# basic.net
KiCad netlist of a schematic drawn in EAGLE
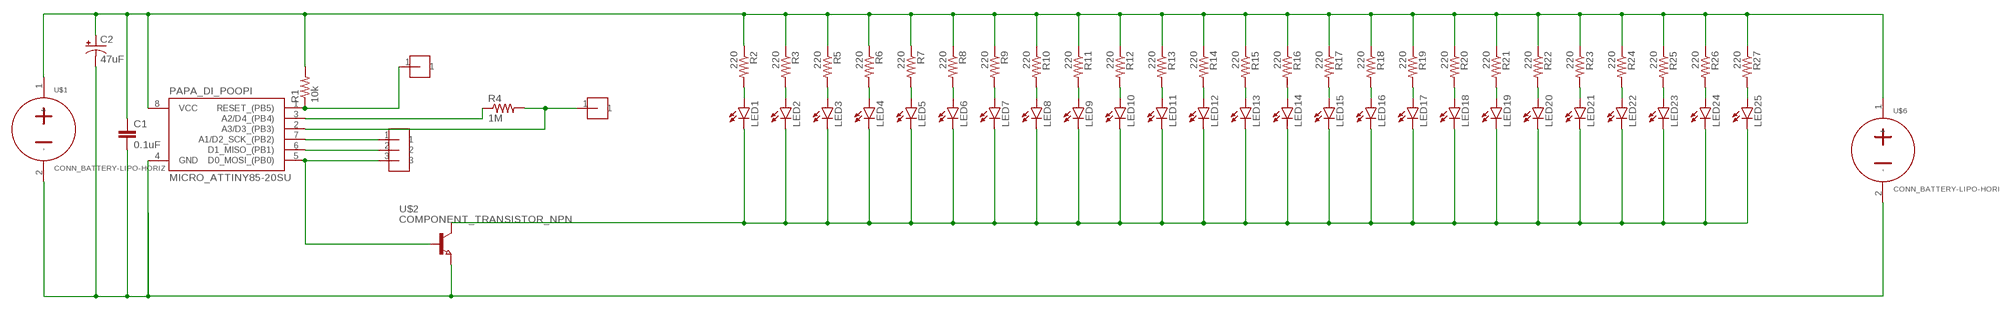
[diagram p0: schematic, sheet 1]

(export (version "E")
  (design (tool "Eeschema 10.0.6"))
  (components
    (comp (ref "C1")
      (value "0.1uF")
      (footprint "eagle-import:0805")
      (libsource (lib "eagle-import") (part "COMPONENT_CAP-0805"))
    )
    (comp (ref "C2")
      (value "47uF")
      (footprint "eagle-import:CAP_RADIAL_CAN_10MM")
      (libsource (lib "eagle-import") (part "COMPONENT_CAP_POL-6.3MM"))
    )
    (comp (ref "CAP_SENSOR_1")
      (value "HEADER-1-TESTPOINT")
      (footprint "eagle-import:TESTPOINT-1")
      (libsource (lib "eagle-import") (part "HEADER-1-TESTPOINT"))
    )
    (comp (ref "CAP_SENSOR_2")
      (value "HEADER-1-TESTPOINT")
      (footprint "eagle-import:TESTPOINT-1")
      (libsource (lib "eagle-import") (part "HEADER-1-TESTPOINT"))
    )
    (comp (ref "LED1")
      (value "LED-0805")
      (footprint "eagle-import:CHIP-LED0805")
      (libsource (lib "eagle-import") (part "LED-0805"))
    )
    (comp (ref "LED2")
      (value "LED-0805")
      (footprint "eagle-import:CHIP-LED0805")
      (libsource (lib "eagle-import") (part "LED-0805"))
    )
    (comp (ref "LED3")
      (value "LED-0805")
      (footprint "eagle-import:CHIP-LED0805")
      (libsource (lib "eagle-import") (part "LED-0805"))
    )
    (comp (ref "LED4")
      (value "LED-0805")
      (footprint "eagle-import:CHIP-LED0805")
      (libsource (lib "eagle-import") (part "LED-0805"))
    )
    (comp (ref "LED5")
      (value "LED-0805")
      (footprint "eagle-import:CHIP-LED0805")
      (libsource (lib "eagle-import") (part "LED-0805"))
    )
    (comp (ref "LED6")
      (value "LED-0805")
      (footprint "eagle-import:CHIP-LED0805")
      (libsource (lib "eagle-import") (part "LED-0805"))
    )
    (comp (ref "LED7")
      (value "LED-0805")
      (footprint "eagle-import:CHIP-LED0805")
      (libsource (lib "eagle-import") (part "LED-0805"))
    )
    (comp (ref "LED8")
      (value "LED-0805")
      (footprint "eagle-import:CHIP-LED0805")
      (libsource (lib "eagle-import") (part "LED-0805"))
    )
    (comp (ref "LED9")
      (value "LED-0805")
      (footprint "eagle-import:CHIP-LED0805")
      (libsource (lib "eagle-import") (part "LED-0805"))
    )
    (comp (ref "LED10")
      (value "LED-0805")
      (footprint "eagle-import:CHIP-LED0805")
      (libsource (lib "eagle-import") (part "LED-0805"))
    )
    (comp (ref "LED11")
      (value "LED-0805")
      (footprint "eagle-import:CHIP-LED0805")
      (libsource (lib "eagle-import") (part "LED-0805"))
    )
    (comp (ref "LED12")
      (value "LED-0805")
      (footprint "eagle-import:CHIP-LED0805")
      (libsource (lib "eagle-import") (part "LED-0805"))
    )
    (comp (ref "LED13")
      (value "LED-0805")
      (footprint "eagle-import:CHIP-LED0805")
      (libsource (lib "eagle-import") (part "LED-0805"))
    )
    (comp (ref "LED14")
      (value "LED-0805")
      (footprint "eagle-import:CHIP-LED0805")
      (libsource (lib "eagle-import") (part "LED-0805"))
    )
    (comp (ref "LED15")
      (value "LED-0805")
      (footprint "eagle-import:CHIP-LED0805")
      (libsource (lib "eagle-import") (part "LED-0805"))
    )
    (comp (ref "LED16")
      (value "LED-0805")
      (footprint "eagle-import:CHIP-LED0805")
      (libsource (lib "eagle-import") (part "LED-0805"))
    )
    (comp (ref "LED17")
      (value "LED-0805")
      (footprint "eagle-import:CHIP-LED0805")
      (libsource (lib "eagle-import") (part "LED-0805"))
    )
    (comp (ref "LED18")
      (value "LED-0805")
      (footprint "eagle-import:CHIP-LED0805")
      (libsource (lib "eagle-import") (part "LED-0805"))
    )
    (comp (ref "LED19")
      (value "LED-0805")
      (footprint "eagle-import:CHIP-LED0805")
      (libsource (lib "eagle-import") (part "LED-0805"))
    )
    (comp (ref "LED20")
      (value "LED-0805")
      (footprint "eagle-import:CHIP-LED0805")
      (libsource (lib "eagle-import") (part "LED-0805"))
    )
    (comp (ref "LED21")
      (value "LED-0805")
      (footprint "eagle-import:CHIP-LED0805")
      (libsource (lib "eagle-import") (part "LED-0805"))
    )
    (comp (ref "LED22")
      (value "LED-0805")
      (footprint "eagle-import:CHIP-LED0805")
      (libsource (lib "eagle-import") (part "LED-0805"))
    )
    (comp (ref "LED23")
      (value "LED-0805")
      (footprint "eagle-import:CHIP-LED0805")
      (libsource (lib "eagle-import") (part "LED-0805"))
    )
    (comp (ref "LED24")
      (value "LED-0805")
      (footprint "eagle-import:CHIP-LED0805")
      (libsource (lib "eagle-import") (part "LED-0805"))
    )
    (comp (ref "LED25")
      (value "LED-0805")
      (footprint "eagle-import:CHIP-LED0805")
      (libsource (lib "eagle-import") (part "LED-0805"))
    )
    (comp (ref "PAPA_DI_POOPI")
      (value "MICRO_ATTINY85-20SU")
      (footprint "eagle-import:SOIC8")
      (libsource (lib "eagle-import") (part "MICRO_ATTINY85-20SU"))
    )
    (comp (ref "R1")
      (value "10k")
      (footprint "eagle-import:0805")
      (libsource (lib "eagle-import") (part "COMPONENT_RESISTOR-0805"))
    )
    (comp (ref "R2")
      (value "220")
      (footprint "eagle-import:0805")
      (libsource (lib "eagle-import") (part "COMPONENT_RESISTOR-0805"))
    )
    (comp (ref "R3")
      (value "220")
      (footprint "eagle-import:0805")
      (libsource (lib "eagle-import") (part "COMPONENT_RESISTOR-0805"))
    )
    (comp (ref "R4")
      (value "1M")
      (footprint "eagle-import:0805")
      (libsource (lib "eagle-import") (part "COMPONENT_RESISTOR-0805"))
    )
    (comp (ref "R5")
      (value "220")
      (footprint "eagle-import:0805")
      (libsource (lib "eagle-import") (part "COMPONENT_RESISTOR-0805"))
    )
    (comp (ref "R6")
      (value "220")
      (footprint "eagle-import:0805")
      (libsource (lib "eagle-import") (part "COMPONENT_RESISTOR-0805"))
    )
    (comp (ref "R7")
      (value "220")
      (footprint "eagle-import:0805")
      (libsource (lib "eagle-import") (part "COMPONENT_RESISTOR-0805"))
    )
    (comp (ref "R8")
      (value "220")
      (footprint "eagle-import:0805")
      (libsource (lib "eagle-import") (part "COMPONENT_RESISTOR-0805"))
    )
    (comp (ref "R9")
      (value "220")
      (footprint "eagle-import:0805")
      (libsource (lib "eagle-import") (part "COMPONENT_RESISTOR-0805"))
    )
    (comp (ref "R10")
      (value "220")
      (footprint "eagle-import:0805")
      (libsource (lib "eagle-import") (part "COMPONENT_RESISTOR-0805"))
    )
    (comp (ref "R11")
      (value "220")
      (footprint "eagle-import:0805")
      (libsource (lib "eagle-import") (part "COMPONENT_RESISTOR-0805"))
    )
    (comp (ref "R12")
      (value "220")
      (footprint "eagle-import:0805")
      (libsource (lib "eagle-import") (part "COMPONENT_RESISTOR-0805"))
    )
    (comp (ref "R13")
      (value "220")
      (footprint "eagle-import:0805")
      (libsource (lib "eagle-import") (part "COMPONENT_RESISTOR-0805"))
    )
    (comp (ref "R14")
      (value "220")
      (footprint "eagle-import:0805")
      (libsource (lib "eagle-import") (part "COMPONENT_RESISTOR-0805"))
    )
    (comp (ref "R15")
      (value "220")
      (footprint "eagle-import:0805")
      (libsource (lib "eagle-import") (part "COMPONENT_RESISTOR-0805"))
    )
    (comp (ref "R16")
      (value "220")
      (footprint "eagle-import:0805")
      (libsource (lib "eagle-import") (part "COMPONENT_RESISTOR-0805"))
    )
    (comp (ref "R17")
      (value "220")
      (footprint "eagle-import:0805")
      (libsource (lib "eagle-import") (part "COMPONENT_RESISTOR-0805"))
    )
    (comp (ref "R18")
      (value "220")
      (footprint "eagle-import:0805")
      (libsource (lib "eagle-import") (part "COMPONENT_RESISTOR-0805"))
    )
    (comp (ref "R19")
      (value "220")
      (footprint "eagle-import:0805")
      (libsource (lib "eagle-import") (part "COMPONENT_RESISTOR-0805"))
    )
    (comp (ref "R20")
      (value "220")
      (footprint "eagle-import:0805")
      (libsource (lib "eagle-import") (part "COMPONENT_RESISTOR-0805"))
    )
    (comp (ref "R21")
      (value "220")
      (footprint "eagle-import:0805")
      (libsource (lib "eagle-import") (part "COMPONENT_RESISTOR-0805"))
    )
    (comp (ref "R22")
      (value "220")
      (footprint "eagle-import:0805")
      (libsource (lib "eagle-import") (part "COMPONENT_RESISTOR-0805"))
    )
    (comp (ref "R23")
      (value "220")
      (footprint "eagle-import:0805")
      (libsource (lib "eagle-import") (part "COMPONENT_RESISTOR-0805"))
    )
    (comp (ref "R24")
      (value "220")
      (footprint "eagle-import:0805")
      (libsource (lib "eagle-import") (part "COMPONENT_RESISTOR-0805"))
    )
    (comp (ref "R25")
      (value "220")
      (footprint "eagle-import:0805")
      (libsource (lib "eagle-import") (part "COMPONENT_RESISTOR-0805"))
    )
    (comp (ref "R26")
      (value "220")
      (footprint "eagle-import:0805")
      (libsource (lib "eagle-import") (part "COMPONENT_RESISTOR-0805"))
    )
    (comp (ref "R27")
      (value "220")
      (footprint "eagle-import:0805")
      (libsource (lib "eagle-import") (part "COMPONENT_RESISTOR-0805"))
    )
    (comp (ref "U$1")
      (value "CONN_BATTERY-LIPO-HORIZ")
      (footprint "eagle-import:JST-PH-2-SMT-RA")
      (libsource (lib "eagle-import") (part "CONN_BATTERY-LIPO-HORIZ"))
    )
    (comp (ref "U$2")
      (value "COMPONENT_TRANSISTOR_NPN")
      (footprint "eagle-import:SOT23")
      (libsource (lib "eagle-import") (part "COMPONENT_TRANSISTOR_NPN"))
    )
    (comp (ref "U$5")
      (value "HEADER-3-TESTPOINT")
      (footprint "eagle-import:TESTPOINT-3")
      (libsource (lib "eagle-import") (part "HEADER-3-TESTPOINT"))
    )
    (comp (ref "U$6")
      (value "CONN_BATTERY-LIPO-HORIZ")
      (footprint "eagle-import:JST-PH-2-SMT-RA")
      (libsource (lib "eagle-import") (part "CONN_BATTERY-LIPO-HORIZ"))
    )
  )
  (nets
    (net (code "1") (name "Net-(LED1-PadA)") (class "Default")
      (node (ref "LED1") (pin "A") (pinfunction "A_A") (pintype "passive"))
      (node (ref "R2") (pin "2") (pinfunction "2_2") (pintype "passive"))
    )
    (net (code "2") (name "Net-(LED2-PadA)") (class "Default")
      (node (ref "LED2") (pin "A") (pinfunction "A_A") (pintype "passive"))
      (node (ref "R3") (pin "2") (pinfunction "2_2") (pintype "passive"))
    )
    (net (code "3") (name "Net-(LED3-PadA)") (class "Default")
      (node (ref "LED3") (pin "A") (pinfunction "A_A") (pintype "passive"))
      (node (ref "R5") (pin "2") (pinfunction "2_2") (pintype "passive"))
    )
    (net (code "4") (name "Net-(LED4-PadA)") (class "Default")
      (node (ref "LED4") (pin "A") (pinfunction "A_A") (pintype "passive"))
      (node (ref "R6") (pin "2") (pinfunction "2_2") (pintype "passive"))
    )
    (net (code "5") (name "Net-(LED5-PadA)") (class "Default")
      (node (ref "LED5") (pin "A") (pinfunction "A_A") (pintype "passive"))
      (node (ref "R7") (pin "2") (pinfunction "2_2") (pintype "passive"))
    )
    (net (code "6") (name "Net-(LED6-PadA)") (class "Default")
      (node (ref "LED6") (pin "A") (pinfunction "A_A") (pintype "passive"))
      (node (ref "R8") (pin "2") (pinfunction "2_2") (pintype "passive"))
    )
    (net (code "7") (name "Net-(LED7-PadA)") (class "Default")
      (node (ref "LED7") (pin "A") (pinfunction "A_A") (pintype "passive"))
      (node (ref "R9") (pin "2") (pinfunction "2_2") (pintype "passive"))
    )
    (net (code "8") (name "Net-(LED8-PadA)") (class "Default")
      (node (ref "LED8") (pin "A") (pinfunction "A_A") (pintype "passive"))
      (node (ref "R10") (pin "2") (pinfunction "2_2") (pintype "passive"))
    )
    (net (code "9") (name "Net-(LED9-PadA)") (class "Default")
      (node (ref "LED9") (pin "A") (pinfunction "A_A") (pintype "passive"))
      (node (ref "R11") (pin "2") (pinfunction "2_2") (pintype "passive"))
    )
    (net (code "10") (name "Net-(LED10-PadA)") (class "Default")
      (node (ref "LED10") (pin "A") (pinfunction "A_A") (pintype "passive"))
      (node (ref "R12") (pin "2") (pinfunction "2_2") (pintype "passive"))
    )
    (net (code "11") (name "Net-(LED11-PadA)") (class "Default")
      (node (ref "LED11") (pin "A") (pinfunction "A_A") (pintype "passive"))
      (node (ref "R13") (pin "2") (pinfunction "2_2") (pintype "passive"))
    )
    (net (code "12") (name "Net-(LED12-PadA)") (class "Default")
      (node (ref "LED12") (pin "A") (pinfunction "A_A") (pintype "passive"))
      (node (ref "R14") (pin "2") (pinfunction "2_2") (pintype "passive"))
    )
    (net (code "13") (name "Net-(LED13-PadA)") (class "Default")
      (node (ref "LED13") (pin "A") (pinfunction "A_A") (pintype "passive"))
      (node (ref "R15") (pin "2") (pinfunction "2_2") (pintype "passive"))
    )
    (net (code "14") (name "Net-(LED14-PadA)") (class "Default")
      (node (ref "LED14") (pin "A") (pinfunction "A_A") (pintype "passive"))
      (node (ref "R16") (pin "2") (pinfunction "2_2") (pintype "passive"))
    )
    (net (code "15") (name "Net-(LED15-PadA)") (class "Default")
      (node (ref "LED15") (pin "A") (pinfunction "A_A") (pintype "passive"))
      (node (ref "R17") (pin "2") (pinfunction "2_2") (pintype "passive"))
    )
    (net (code "16") (name "Net-(LED16-PadA)") (class "Default")
      (node (ref "LED16") (pin "A") (pinfunction "A_A") (pintype "passive"))
      (node (ref "R18") (pin "2") (pinfunction "2_2") (pintype "passive"))
    )
    (net (code "17") (name "Net-(LED17-PadA)") (class "Default")
      (node (ref "LED17") (pin "A") (pinfunction "A_A") (pintype "passive"))
      (node (ref "R19") (pin "2") (pinfunction "2_2") (pintype "passive"))
    )
    (net (code "18") (name "Net-(LED18-PadA)") (class "Default")
      (node (ref "LED18") (pin "A") (pinfunction "A_A") (pintype "passive"))
      (node (ref "R20") (pin "2") (pinfunction "2_2") (pintype "passive"))
    )
    (net (code "19") (name "Net-(LED19-PadA)") (class "Default")
      (node (ref "LED19") (pin "A") (pinfunction "A_A") (pintype "passive"))
      (node (ref "R21") (pin "2") (pinfunction "2_2") (pintype "passive"))
    )
    (net (code "20") (name "Net-(LED20-PadA)") (class "Default")
      (node (ref "LED20") (pin "A") (pinfunction "A_A") (pintype "passive"))
      (node (ref "R22") (pin "2") (pinfunction "2_2") (pintype "passive"))
    )
    (net (code "21") (name "Net-(LED21-PadA)") (class "Default")
      (node (ref "LED21") (pin "A") (pinfunction "A_A") (pintype "passive"))
      (node (ref "R23") (pin "2") (pinfunction "2_2") (pintype "passive"))
    )
    (net (code "22") (name "Net-(LED22-PadA)") (class "Default")
      (node (ref "LED22") (pin "A") (pinfunction "A_A") (pintype "passive"))
      (node (ref "R24") (pin "2") (pinfunction "2_2") (pintype "passive"))
    )
    (net (code "23") (name "Net-(LED23-PadA)") (class "Default")
      (node (ref "LED23") (pin "A") (pinfunction "A_A") (pintype "passive"))
      (node (ref "R25") (pin "2") (pinfunction "2_2") (pintype "passive"))
    )
    (net (code "24") (name "Net-(LED24-PadA)") (class "Default")
      (node (ref "LED24") (pin "A") (pinfunction "A_A") (pintype "passive"))
      (node (ref "R26") (pin "2") (pinfunction "2_2") (pintype "passive"))
    )
    (net (code "25") (name "Net-(LED25-PadA)") (class "Default")
      (node (ref "LED25") (pin "A") (pinfunction "A_A") (pintype "passive"))
      (node (ref "R27") (pin "2") (pinfunction "2_2") (pintype "passive"))
    )
    (net (code "26") (name "Net-(PAPA_DI_POOPI-A1{slash}D2_SCK_(PB2))") (class "Default")
      (node (ref "PAPA_DI_POOPI") (pin "7") (pinfunction "A1/D2_SCK_(PB2)_7") (pintype "bidirectional"))
      (node (ref "U$5") (pin "1") (pinfunction "1_1") (pintype "bidirectional"))
    )
    (net (code "27") (name "Net-(PAPA_DI_POOPI-A2{slash}D4_(PB4))") (class "Default")
      (node (ref "PAPA_DI_POOPI") (pin "3") (pinfunction "A2/D4_(PB4)_3") (pintype "bidirectional"))
      (node (ref "R4") (pin "1") (pinfunction "1_1") (pintype "passive"))
    )
    (net (code "28") (name "Net-(PAPA_DI_POOPI-A3{slash}D3_(PB3))") (class "Default")
      (node (ref "CAP_SENSOR_2") (pin "1") (pinfunction "1_1") (pintype "bidirectional"))
      (node (ref "PAPA_DI_POOPI") (pin "2") (pinfunction "A3/D3_(PB3)_2") (pintype "bidirectional"))
      (node (ref "R4") (pin "2") (pinfunction "2_2") (pintype "passive"))
    )
    (net (code "29") (name "Net-(PAPA_DI_POOPI-D0_MOSI_(PB0))") (class "Default")
      (node (ref "PAPA_DI_POOPI") (pin "5") (pinfunction "D0_MOSI_(PB0)_5") (pintype "bidirectional"))
      (node (ref "U$2") (pin "1") (pinfunction "B_1") (pintype "passive"))
      (node (ref "U$5") (pin "3") (pinfunction "3_3") (pintype "bidirectional"))
    )
    (net (code "30") (name "Net-(PAPA_DI_POOPI-D1_MISO_(PB1))") (class "Default")
      (node (ref "PAPA_DI_POOPI") (pin "6") (pinfunction "D1_MISO_(PB1)_6") (pintype "bidirectional"))
      (node (ref "U$5") (pin "2") (pinfunction "2_2") (pintype "bidirectional"))
    )
    (net (code "31") (name "Net-(PAPA_DI_POOPI-GND)") (class "Default")
      (node (ref "C1") (pin "2") (pinfunction "2_2") (pintype "passive"))
      (node (ref "C2") (pin "-") (pinfunction "-_-") (pintype "passive"))
      (node (ref "PAPA_DI_POOPI") (pin "4") (pinfunction "GND_4") (pintype "power_in"))
      (node (ref "U$1") (pin "2") (pinfunction "-_2") (pintype "bidirectional"))
      (node (ref "U$2") (pin "2") (pinfunction "E_2") (pintype "passive"))
      (node (ref "U$6") (pin "2") (pinfunction "-_2") (pintype "bidirectional"))
    )
    (net (code "32") (name "Net-(PAPA_DI_POOPI-RESET_(PB5))") (class "Default")
      (node (ref "CAP_SENSOR_1") (pin "1") (pinfunction "1_1") (pintype "bidirectional"))
      (node (ref "PAPA_DI_POOPI") (pin "1") (pinfunction "RESET_(PB5)_1") (pintype "bidirectional"))
      (node (ref "R1") (pin "1") (pinfunction "1_1") (pintype "passive"))
    )
    (net (code "33") (name "Net-(PAPA_DI_POOPI-VCC)") (class "Default")
      (node (ref "C1") (pin "1") (pinfunction "1_1") (pintype "passive"))
      (node (ref "C2") (pin "+") (pinfunction "+_+") (pintype "passive"))
      (node (ref "PAPA_DI_POOPI") (pin "8") (pinfunction "VCC_8") (pintype "power_in"))
      (node (ref "R1") (pin "2") (pinfunction "2_2") (pintype "passive"))
      (node (ref "R10") (pin "1") (pinfunction "1_1") (pintype "passive"))
      (node (ref "R11") (pin "1") (pinfunction "1_1") (pintype "passive"))
      (node (ref "R12") (pin "1") (pinfunction "1_1") (pintype "passive"))
      (node (ref "R13") (pin "1") (pinfunction "1_1") (pintype "passive"))
      (node (ref "R14") (pin "1") (pinfunction "1_1") (pintype "passive"))
      (node (ref "R15") (pin "1") (pinfunction "1_1") (pintype "passive"))
      (node (ref "R16") (pin "1") (pinfunction "1_1") (pintype "passive"))
      (node (ref "R17") (pin "1") (pinfunction "1_1") (pintype "passive"))
      (node (ref "R18") (pin "1") (pinfunction "1_1") (pintype "passive"))
      (node (ref "R19") (pin "1") (pinfunction "1_1") (pintype "passive"))
      (node (ref "R2") (pin "1") (pinfunction "1_1") (pintype "passive"))
      (node (ref "R20") (pin "1") (pinfunction "1_1") (pintype "passive"))
      (node (ref "R21") (pin "1") (pinfunction "1_1") (pintype "passive"))
      (node (ref "R22") (pin "1") (pinfunction "1_1") (pintype "passive"))
      (node (ref "R23") (pin "1") (pinfunction "1_1") (pintype "passive"))
      (node (ref "R24") (pin "1") (pinfunction "1_1") (pintype "passive"))
      (node (ref "R25") (pin "1") (pinfunction "1_1") (pintype "passive"))
      (node (ref "R26") (pin "1") (pinfunction "1_1") (pintype "passive"))
      (node (ref "R27") (pin "1") (pinfunction "1_1") (pintype "passive"))
      (node (ref "R3") (pin "1") (pinfunction "1_1") (pintype "passive"))
      (node (ref "R5") (pin "1") (pinfunction "1_1") (pintype "passive"))
      (node (ref "R6") (pin "1") (pinfunction "1_1") (pintype "passive"))
      (node (ref "R7") (pin "1") (pinfunction "1_1") (pintype "passive"))
      (node (ref "R8") (pin "1") (pinfunction "1_1") (pintype "passive"))
      (node (ref "R9") (pin "1") (pinfunction "1_1") (pintype "passive"))
      (node (ref "U$1") (pin "1") (pinfunction "+_1") (pintype "bidirectional"))
      (node (ref "U$6") (pin "1") (pinfunction "+_1") (pintype "bidirectional"))
    )
    (net (code "34") (name "Net-(U$2-C)") (class "Default")
      (node (ref "LED1") (pin "C") (pinfunction "C_C") (pintype "passive"))
      (node (ref "LED10") (pin "C") (pinfunction "C_C") (pintype "passive"))
      (node (ref "LED11") (pin "C") (pinfunction "C_C") (pintype "passive"))
      (node (ref "LED12") (pin "C") (pinfunction "C_C") (pintype "passive"))
      (node (ref "LED13") (pin "C") (pinfunction "C_C") (pintype "passive"))
      (node (ref "LED14") (pin "C") (pinfunction "C_C") (pintype "passive"))
      (node (ref "LED15") (pin "C") (pinfunction "C_C") (pintype "passive"))
      (node (ref "LED16") (pin "C") (pinfunction "C_C") (pintype "passive"))
      (node (ref "LED17") (pin "C") (pinfunction "C_C") (pintype "passive"))
      (node (ref "LED18") (pin "C") (pinfunction "C_C") (pintype "passive"))
      (node (ref "LED19") (pin "C") (pinfunction "C_C") (pintype "passive"))
      (node (ref "LED2") (pin "C") (pinfunction "C_C") (pintype "passive"))
      (node (ref "LED20") (pin "C") (pinfunction "C_C") (pintype "passive"))
      (node (ref "LED21") (pin "C") (pinfunction "C_C") (pintype "passive"))
      (node (ref "LED22") (pin "C") (pinfunction "C_C") (pintype "passive"))
      (node (ref "LED23") (pin "C") (pinfunction "C_C") (pintype "passive"))
      (node (ref "LED24") (pin "C") (pinfunction "C_C") (pintype "passive"))
      (node (ref "LED25") (pin "C") (pinfunction "C_C") (pintype "passive"))
      (node (ref "LED3") (pin "C") (pinfunction "C_C") (pintype "passive"))
      (node (ref "LED4") (pin "C") (pinfunction "C_C") (pintype "passive"))
      (node (ref "LED5") (pin "C") (pinfunction "C_C") (pintype "passive"))
      (node (ref "LED6") (pin "C") (pinfunction "C_C") (pintype "passive"))
      (node (ref "LED7") (pin "C") (pinfunction "C_C") (pintype "passive"))
      (node (ref "LED8") (pin "C") (pinfunction "C_C") (pintype "passive"))
      (node (ref "LED9") (pin "C") (pinfunction "C_C") (pintype "passive"))
      (node (ref "U$2") (pin "3") (pinfunction "C_3") (pintype "passive"))
    )
  )
)
